# 12_SATA.net
KiCad netlist of a schematic drawn in Altium Designer
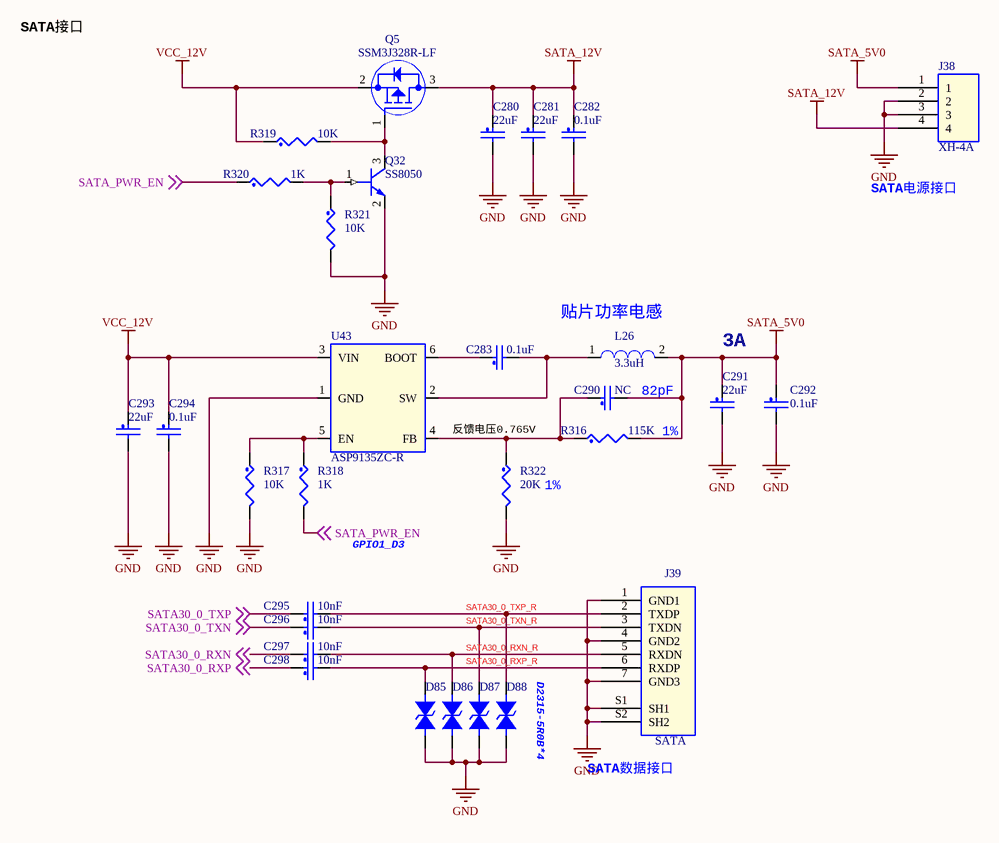
[diagram p0: 12.SATA接口.SchDoc]

(export (version "E")
  (design (tool "Eeschema 10.0.6"))
  (components
    (comp (ref "C280") (value "22uF") (footprint "0.PCB1:C0805") (libsource (lib "RK3588底板") (part "CAP_NP")))
    (comp (ref "C281") (value "22uF") (footprint "0.PCB1:C0805") (libsource (lib "RK3588底板") (part "CAP_NP")))
    (comp (ref "C282")
      (value "0.1uF")
      (footprint "0.PCB1:C0402")
      (libsource (lib "RK3588底板") (part "CAP_NP"))
    )
    (comp (ref "C283")
      (value "0.1uF")
      (footprint "0.PCB1:C0402")
      (libsource (lib "RK3588底板") (part "CAP_NP"))
    )
    (comp (ref "C290") (value "NC") (footprint "0.PCB1:C0402") (libsource (lib "RK3588底板") (part "CAP_NP")))
    (comp (ref "C291") (value "22uF") (footprint "0.PCB1:C0603") (libsource (lib "RK3588底板") (part "CAP_NP")))
    (comp (ref "C292")
      (value "0.1uF")
      (footprint "0.PCB1:C0402")
      (libsource (lib "RK3588底板") (part "CAP_NP"))
    )
    (comp (ref "C293") (value "22uF") (footprint "0.PCB1:C0603") (libsource (lib "RK3588底板") (part "CAP_NP")))
    (comp (ref "C294")
      (value "0.1uF")
      (footprint "0.PCB1:C0402")
      (libsource (lib "RK3588底板") (part "CAP_NP"))
    )
    (comp (ref "C295") (value "10nF") (footprint "0.PCB1:C0402") (libsource (lib "RK3588底板") (part "CAP_NP")))
    (comp (ref "C296") (value "10nF") (footprint "0.PCB1:C0402") (libsource (lib "RK3588底板") (part "CAP_NP")))
    (comp (ref "C297") (value "10nF") (footprint "0.PCB1:C0402") (libsource (lib "RK3588底板") (part "CAP_NP")))
    (comp (ref "C298") (value "10nF") (footprint "0.PCB1:C0402") (libsource (lib "RK3588底板") (part "CAP_NP")))
    (comp (ref "D85")
      (value "D2315-5R0B")
      (footprint "0.PCB1:esd0402")
      (libsource (lib "RK3588底板") (part "DIODE BI-DIR TRIG"))
    )
    (comp (ref "D86")
      (value "D2315-5R0B")
      (footprint "0.PCB1:esd0402")
      (libsource (lib "RK3588底板") (part "DIODE BI-DIR TRIG"))
    )
    (comp (ref "D87")
      (value "D2315-5R0B")
      (footprint "0.PCB1:esd0402")
      (libsource (lib "RK3588底板") (part "DIODE BI-DIR TRIG"))
    )
    (comp (ref "D88")
      (value "D2315-5R0B")
      (footprint "0.PCB1:esd0402")
      (libsource (lib "RK3588底板") (part "DIODE BI-DIR TRIG"))
    )
    (comp (ref "J38")
      (value "XH-4A")
      (footprint "0.PCB1:XH2p54-4p")
      (libsource (lib "RK3588底板") (part "1X4PIN"))
    )
    (comp (ref "J39") (value "SATA") (footprint "0.PCB1:ssata_v") (libsource (lib "RK3588底板") (part "SATA")))
    (comp (ref "L26") (value "3.3uH") (footprint "0.PCB1:l4520") (libsource (lib "RK3588底板") (part "IND")))
    (comp (ref "Q5")
      (value "SSM3J328R-LF")
      (footprint "0.PCB1:SOT23")
      (libsource (lib "RK3588底板") (part "MOSFET_P"))
    )
    (comp (ref "Q32") (value "SS8050") (footprint "0.PCB1:SOT23") (libsource (lib "RK3588底板") (part "NPN")))
    (comp (ref "R316") (value "115K") (footprint "0.PCB1:R0402") (libsource (lib "RK3588底板") (part "RES")))
    (comp (ref "R317") (value "10K") (footprint "0.PCB1:R0402") (libsource (lib "RK3588底板") (part "RES")))
    (comp (ref "R318") (value "1K") (footprint "0.PCB1:R0402") (libsource (lib "RK3588底板") (part "RES")))
    (comp (ref "R319") (value "10K") (footprint "0.PCB1:R0402") (libsource (lib "RK3588底板") (part "RES")))
    (comp (ref "R320") (value "1K") (footprint "0.PCB1:R0402") (libsource (lib "RK3588底板") (part "RES")))
    (comp (ref "R321") (value "10K") (footprint "0.PCB1:R0402") (libsource (lib "RK3588底板") (part "RES")))
    (comp (ref "R322") (value "20K") (footprint "0.PCB1:R0402") (libsource (lib "RK3588底板") (part "RES")))
    (comp (ref "U43")
      (value "ASP9135ZC-R")
      (footprint "0.PCB1:SOT23_6")
      (libsource (lib "RK3588底板") (part "TP6327GS6"))
    )
  )
  (nets
    (net (code "1") (name "/SATA30_0_RXN_R") (class "Default")
      (node (ref "C297") (pin "2") (pinfunction "2_2") (pintype "passive"))
      (node (ref "D86") (pin "2") (pinfunction "2_2") (pintype "passive"))
      (node (ref "J39") (pin "5") (pinfunction "RXDN_5") (pintype "passive"))
    )
    (net (code "2") (name "/SATA30_0_RXP_R") (class "Default")
      (node (ref "C298") (pin "2") (pinfunction "2_2") (pintype "passive"))
      (node (ref "D85") (pin "2") (pinfunction "2_2") (pintype "passive"))
      (node (ref "J39") (pin "6") (pinfunction "RXDP_6") (pintype "passive"))
    )
    (net (code "3") (name "/SATA30_0_TXN_R") (class "Default")
      (node (ref "C296") (pin "2") (pinfunction "2_2") (pintype "passive"))
      (node (ref "D87") (pin "2") (pinfunction "2_2") (pintype "passive"))
      (node (ref "J39") (pin "3") (pinfunction "TXDN_3") (pintype "passive"))
    )
    (net (code "4") (name "/SATA30_0_TXP_R") (class "Default")
      (node (ref "C295") (pin "2") (pinfunction "2_2") (pintype "passive"))
      (node (ref "D88") (pin "2") (pinfunction "2_2") (pintype "passive"))
      (node (ref "J39") (pin "2") (pinfunction "TXDP_2") (pintype "passive"))
    )
    (net (code "5") (name "GND") (class "Default")
      (node (ref "C280") (pin "2") (pinfunction "2_2") (pintype "passive"))
      (node (ref "C281") (pin "2") (pinfunction "2_2") (pintype "passive"))
      (node (ref "C282") (pin "2") (pinfunction "2_2") (pintype "passive"))
      (node (ref "C291") (pin "2") (pinfunction "2_2") (pintype "passive"))
      (node (ref "C292") (pin "2") (pinfunction "2_2") (pintype "passive"))
      (node (ref "C293") (pin "2") (pinfunction "2_2") (pintype "passive"))
      (node (ref "C294") (pin "2") (pinfunction "2_2") (pintype "passive"))
      (node (ref "D85") (pin "1") (pinfunction "1_1") (pintype "passive"))
      (node (ref "D86") (pin "1") (pinfunction "1_1") (pintype "passive"))
      (node (ref "D87") (pin "1") (pinfunction "1_1") (pintype "passive"))
      (node (ref "D88") (pin "1") (pinfunction "1_1") (pintype "passive"))
      (node (ref "J38") (pin "2") (pinfunction "2_2") (pintype "passive"))
      (node (ref "J38") (pin "3") (pinfunction "3_3") (pintype "passive"))
      (node (ref "J39") (pin "1") (pinfunction "GND1_1") (pintype "passive"))
      (node (ref "J39") (pin "4") (pinfunction "GND2_4") (pintype "passive"))
      (node (ref "J39") (pin "7") (pinfunction "GND3_7") (pintype "passive"))
      (node (ref "J39") (pin "S1") (pinfunction "SH1_S1") (pintype "power_in"))
      (node (ref "J39") (pin "S2") (pinfunction "SH2_S2") (pintype "power_in"))
      (node (ref "Q32") (pin "2") (pinfunction "EMITTER_2") (pintype "passive"))
      (node (ref "R317") (pin "2") (pinfunction "2_2") (pintype "passive"))
      (node (ref "R321") (pin "2") (pinfunction "2_2") (pintype "passive"))
      (node (ref "R322") (pin "2") (pinfunction "2_2") (pintype "passive"))
      (node (ref "U43") (pin "1") (pinfunction "GND_1") (pintype "passive"))
    )
    (net (code "6") (name "Net-(Q32-BASE)") (class "Default")
      (node (ref "Q32") (pin "1") (pinfunction "BASE_1") (pintype "input"))
      (node (ref "R320") (pin "2") (pinfunction "2_2") (pintype "passive"))
      (node (ref "R321") (pin "1") (pinfunction "1_1") (pintype "passive"))
    )
    (net (code "7") (name "Net-(Q32-COLLECTOR)") (class "Default")
      (node (ref "Q32") (pin "3") (pinfunction "COLLECTOR_3") (pintype "passive"))
      (node (ref "Q5") (pin "1") (pinfunction "GATE_1") (pintype "passive"))
      (node (ref "R319") (pin "2") (pinfunction "2_2") (pintype "passive"))
    )
    (net (code "8") (name "Net-(U43-BOOT)") (class "Default")
      (node (ref "C283") (pin "1") (pinfunction "1_1") (pintype "passive"))
      (node (ref "U43") (pin "6") (pinfunction "BOOT_6") (pintype "passive"))
    )
    (net (code "9") (name "Net-(U43-EN)") (class "Default")
      (node (ref "R317") (pin "1") (pinfunction "1_1") (pintype "passive"))
      (node (ref "R318") (pin "1") (pinfunction "1_1") (pintype "passive"))
      (node (ref "U43") (pin "5") (pinfunction "EN_5") (pintype "passive"))
    )
    (net (code "10") (name "Net-(U43-FB)") (class "Default")
      (node (ref "C290") (pin "1") (pinfunction "1_1") (pintype "passive"))
      (node (ref "R316") (pin "1") (pinfunction "1_1") (pintype "passive"))
      (node (ref "R322") (pin "1") (pinfunction "1_1") (pintype "passive"))
      (node (ref "U43") (pin "4") (pinfunction "FB_4") (pintype "passive"))
    )
    (net (code "11") (name "Net-(U43-SW)") (class "Default")
      (node (ref "C283") (pin "2") (pinfunction "2_2") (pintype "passive"))
      (node (ref "L26") (pin "1") (pinfunction "1_1") (pintype "passive"))
      (node (ref "U43") (pin "2") (pinfunction "SW_2") (pintype "passive"))
    )
    (net (code "12") (name "SATA30_0_RXN") (class "Default")
      (node (ref "C297") (pin "1") (pinfunction "1_1") (pintype "passive"))
    )
    (net (code "13") (name "SATA30_0_RXP") (class "Default")
      (node (ref "C298") (pin "1") (pinfunction "1_1") (pintype "passive"))
    )
    (net (code "14") (name "SATA30_0_TXN") (class "Default")
      (node (ref "C296") (pin "1") (pinfunction "1_1") (pintype "passive"))
    )
    (net (code "15") (name "SATA30_0_TXP") (class "Default")
      (node (ref "C295") (pin "1") (pinfunction "1_1") (pintype "passive"))
    )
    (net (code "16") (name "SATA_5V0") (class "Default")
      (node (ref "C290") (pin "2") (pinfunction "2_2") (pintype "passive"))
      (node (ref "C291") (pin "1") (pinfunction "1_1") (pintype "passive"))
      (node (ref "C292") (pin "1") (pinfunction "1_1") (pintype "passive"))
      (node (ref "J38") (pin "1") (pinfunction "1_1") (pintype "passive"))
      (node (ref "L26") (pin "2") (pinfunction "2_2") (pintype "passive"))
      (node (ref "R316") (pin "2") (pinfunction "2_2") (pintype "passive"))
    )
    (net (code "17") (name "SATA_12V") (class "Default")
      (node (ref "C280") (pin "1") (pinfunction "1_1") (pintype "passive"))
      (node (ref "C281") (pin "1") (pinfunction "1_1") (pintype "passive"))
      (node (ref "C282") (pin "1") (pinfunction "1_1") (pintype "passive"))
      (node (ref "J38") (pin "4") (pinfunction "4_4") (pintype "passive"))
      (node (ref "Q5") (pin "3") (pinfunction "DRAIN_3") (pintype "passive"))
    )
    (net (code "18") (name "SATA_PWR_EN") (class "Default")
      (node (ref "R318") (pin "2") (pinfunction "2_2") (pintype "passive"))
      (node (ref "R320") (pin "1") (pinfunction "1_1") (pintype "passive"))
    )
    (net (code "19") (name "VCC_12V") (class "Default")
      (node (ref "C293") (pin "1") (pinfunction "1_1") (pintype "passive"))
      (node (ref "C294") (pin "1") (pinfunction "1_1") (pintype "passive"))
      (node (ref "Q5") (pin "2") (pinfunction "SOURCE_2") (pintype "passive"))
      (node (ref "R319") (pin "1") (pinfunction "1_1") (pintype "passive"))
      (node (ref "U43") (pin "3") (pinfunction "VIN_3") (pintype "passive"))
    )
  )
)
